# Encoder_Sheet2.net
KiCad netlist of a schematic drawn in Altium Designer
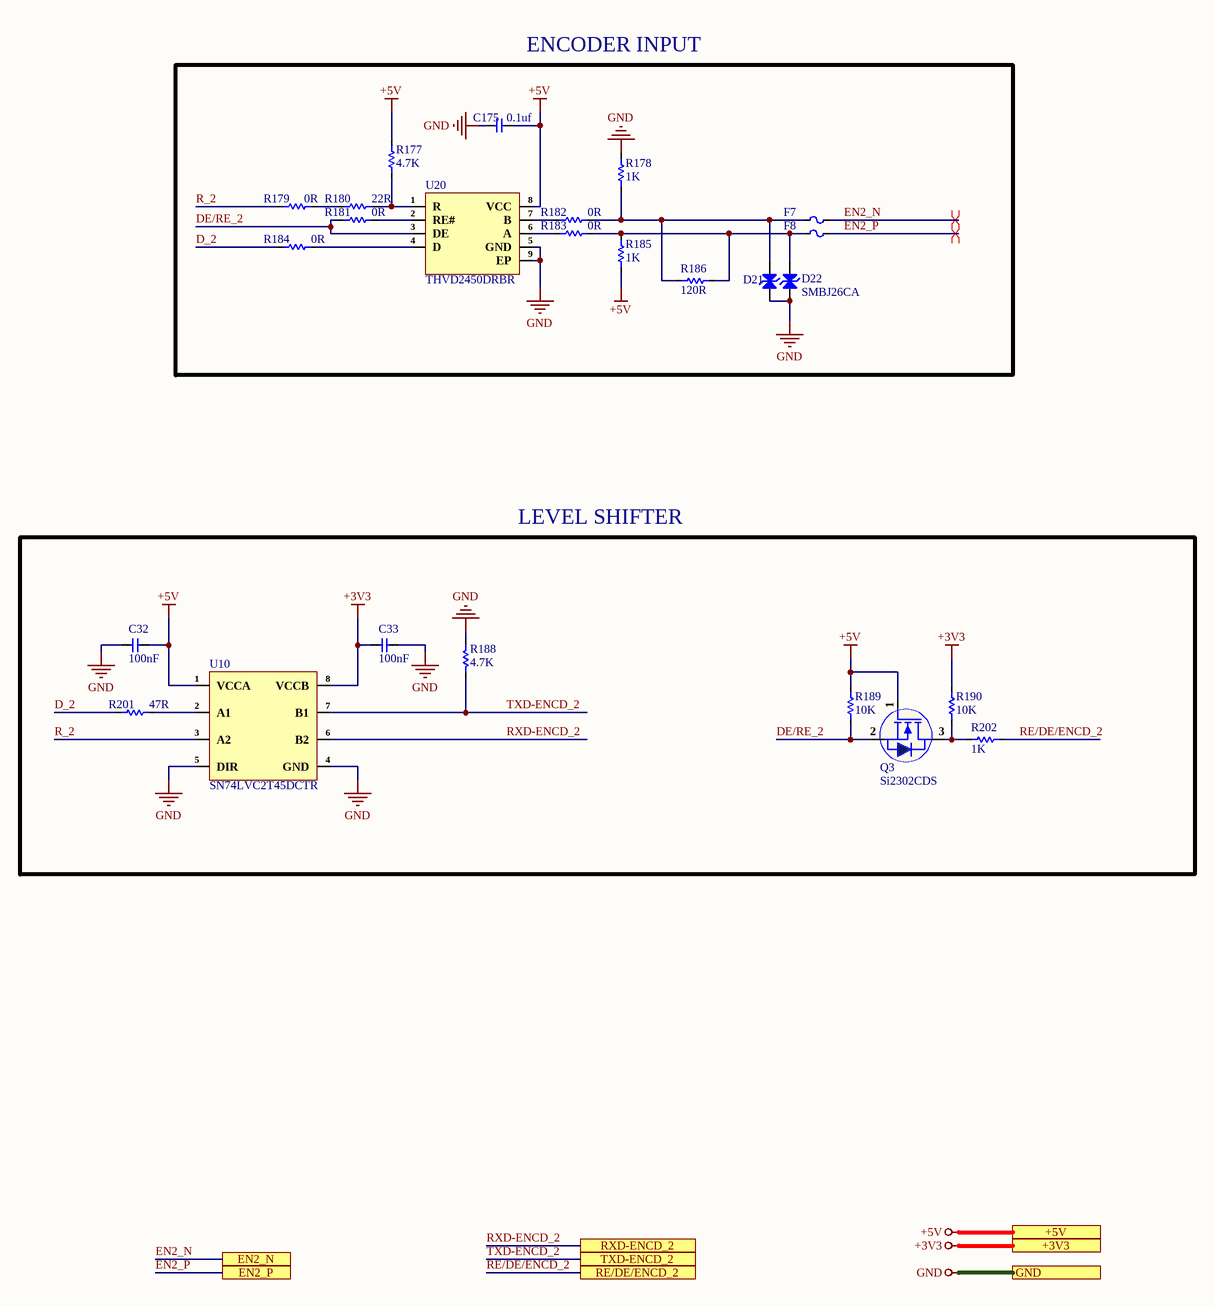
[diagram p0: Encoder_Sheet2.SchDoc]

(export (version "E")
  (design (tool "Eeschema 10.0.6"))
  (components
    (comp (ref "C32")
      (value "100nF")
      (footprint "cap-0402")
      (description "CAP CER 0.1UF 50V X7R 0402")
      (fields
        (field (name "MANUFACTURER") "TDK")
        (field (name "MANUFACTURER PART NUMBER") "C1005X7R1H104KT000F")
      )
      (libsource (lib "eSpark Libraries") (part "C1005X7R1H104KT000F"))
    )
    (comp (ref "C33")
      (value "100nF")
      (footprint "cap-0402")
      (description "CAP CER 0.1UF 50V X7R 0402")
      (fields
        (field (name "MANUFACTURER") "TDK")
        (field (name "MANUFACTURER PART NUMBER") "C1005X7R1H104KT000F")
      )
      (libsource (lib "eSpark Libraries") (part "C1005X7R1H104KT000F"))
    )
    (comp (ref "C175")
      (value "0.1uf")
      (footprint "Cap-0402")
      (description "CAP CER 0.1UF 100V X5R 0402")
      (fields
        (field (name "MANUFACTURER") "Murata")
        (field (name "MANUFACTURER PART NUMBER") "GRM155R62A104KE14D")
      )
      (libsource (lib "eSpark Libraries") (part "GRM155R62A104KE14D"))
    )
    (comp (ref "D21")
      (value "SMBJ26CA")
      (footprint "SMB Bi Directional")
      (description "SMB(DO-214AA) TVS ROHS")
      (fields (field (name "MANUFACTURER") "MSKSEMI") (field (name "LCSC PART NUMBER") "C5331111"))
      (libsource (lib "eSpark Libraries") (part "SMBJ26CA"))
    )
    (comp (ref "D22")
      (value "SMBJ26CA")
      (footprint "SMB Bi Directional")
      (description "SMB(DO-214AA) TVS ROHS")
      (fields (field (name "MANUFACTURER") "MSKSEMI") (field (name "LCSC PART NUMBER") "C5331111"))
      (libsource (lib "eSpark Libraries") (part "SMBJ26CA"))
    )
    (comp (ref "F7")
      (value "SMD0805P020TF")
      (footprint "Fuse-0805")
      (description "9V 200mA 100A 500mA 0805 Resettable Fuses ROHS")
      (fields (field (name "MANUFACTURER") "RUILON") (field (name "LCSC PART NUMBER") "C20976"))
      (libsource (lib "eSpark_centralized_Library(2022)") (part "SMD0805P020TF"))
    )
    (comp (ref "F8")
      (value "SMD0805P020TF")
      (footprint "Fuse-0805")
      (description "9V 200mA 100A 500mA 0805 Resettable Fuses ROHS")
      (fields (field (name "MANUFACTURER") "RUILON") (field (name "LCSC PART NUMBER") "C20976"))
      (libsource (lib "eSpark_centralized_Library(2022)") (part "SMD0805P020TF"))
    )
    (comp (ref "Q3")
      (value "Si2302CDS")
      (footprint "Sot-23")
      (description "N-CHANNEL 20-V (D-S) MOSFET")
      (fields
        (field (name "MANUFACTURER") "TECH PUBLIC")
        (field (name "MANUFACTURER PART NUMBER") "SI2302CDS")
      )
      (libsource (lib "eSpark_centralized_Library(2022)") (part "Si2302CDS"))
    )
    (comp (ref "R177")
      (value "4.7K")
      (footprint "Res-0402")
      (description "RES 4.7K OHM 1% 1/16W 0402")
      (fields
        (field (name "MANUFACTURER") "Yageo")
        (field (name "MANUFACTURER PART NUMBER") "RC0402FR-074K7L")
      )
      (libsource (lib "eSpark Libraries") (part "RC0402FR-074K7L"))
    )
    (comp (ref "R178")
      (value "1K")
      (footprint "Res-0402")
      (description "RES 1K OHM 1% 1/16W 0402")
      (fields
        (field (name "MANUFACTURER") "Yageo")
        (field (name "MANUFACTURER PART NUMBER") "RC0402FR-071KL")
      )
      (libsource (lib "eSpark Libraries") (part "RC0402FR-071KL"))
    )
    (comp (ref "R179")
      (value "0R")
      (footprint "Res-0603")
      (description "RES 0 OHM JUMPER 1/10W 0603")
      (fields
        (field (name "MANUFACTURER") "Yageo")
        (field (name "MANUFACTURER PART NUMBER") "RC0603JR-070RL")
      )
      (libsource (lib "eSpark Libraries") (part "RC0603JR-070RL"))
    )
    (comp (ref "R180")
      (value "22R")
      (footprint "Res-0402")
      (description "RES 22 OHM 1% 1/16W 0402")
      (fields
        (field (name "MANUFACTURER") "Yageo")
        (field (name "MANUFACTURER PART NUMBER") "RC0402FR-0722RL")
      )
      (libsource (lib "eSpark Libraries") (part "RC0402FR-0722RL"))
    )
    (comp (ref "R181")
      (value "0R")
      (footprint "Res-0603")
      (description "RES 0 OHM JUMPER 1/10W 0603")
      (fields
        (field (name "MANUFACTURER") "Yageo")
        (field (name "MANUFACTURER PART NUMBER") "RC0603JR-070RL")
      )
      (libsource (lib "eSpark Libraries") (part "RC0603JR-070RL"))
    )
    (comp (ref "R182")
      (value "0R")
      (footprint "Res-0603")
      (description "RES 0 OHM JUMPER 1/10W 0603")
      (fields
        (field (name "MANUFACTURER") "Yageo")
        (field (name "MANUFACTURER PART NUMBER") "RC0603JR-070RL")
      )
      (libsource (lib "eSpark Libraries") (part "RC0603JR-070RL"))
    )
    (comp (ref "R183")
      (value "0R")
      (footprint "Res-0603")
      (description "RES 0 OHM JUMPER 1/10W 0603")
      (fields
        (field (name "MANUFACTURER") "Yageo")
        (field (name "MANUFACTURER PART NUMBER") "RC0603JR-070RL")
      )
      (libsource (lib "eSpark Libraries") (part "RC0603JR-070RL"))
    )
    (comp (ref "R184")
      (value "0R")
      (footprint "Res-0603")
      (description "RES 0 OHM JUMPER 1/10W 0603")
      (fields
        (field (name "MANUFACTURER") "Yageo")
        (field (name "MANUFACTURER PART NUMBER") "RC0603JR-070RL")
      )
      (libsource (lib "eSpark Libraries") (part "RC0603JR-070RL"))
    )
    (comp (ref "R185")
      (value "1K")
      (footprint "Res-0402")
      (description "RES 1K OHM 1% 1/16W 0402")
      (fields
        (field (name "MANUFACTURER") "Yageo")
        (field (name "MANUFACTURER PART NUMBER") "RC0402FR-071KL")
      )
      (libsource (lib "eSpark Libraries") (part "RC0402FR-071KL"))
    )
    (comp (ref "R186")
      (value "120R")
      (footprint "Res-0402")
      (description "RES 120 OHM 1% 1/16W 0402")
      (fields
        (field (name "MANUFACTURER") "Yageo")
        (field (name "MANUFACTURER PART NUMBER") "RC0402FR-07120RL")
      )
      (libsource (lib "eSpark Libraries") (part "RC0402FR-07120RL"))
    )
    (comp (ref "R188")
      (value "4.7K")
      (footprint "Res-0402")
      (description "RES 4.7K OHM 1% 1/16W 0402")
      (fields
        (field (name "MANUFACTURER") "Yageo")
        (field (name "MANUFACTURER PART NUMBER") "RC0402FR-074K7L")
      )
      (libsource (lib "eSpark Libraries") (part "RC0402FR-074K7L"))
    )
    (comp (ref "R189")
      (value "10K")
      (footprint "Res-0402")
      (description "RES 10K OHM 1% 1/16W 0402")
      (fields
        (field (name "MANUFACTURER") "Yageo")
        (field (name "MANUFACTURER PART NUMBER") "RC0402FR-0710KL")
      )
      (libsource (lib "eSpark_centralized_Library(2022)") (part "RC0402FR-0710KL"))
    )
    (comp (ref "R190")
      (value "10K")
      (footprint "Res-0402")
      (description "RES 10K OHM 1% 1/16W 0402")
      (fields
        (field (name "MANUFACTURER") "Yageo")
        (field (name "MANUFACTURER PART NUMBER") "RC0402FR-0710KL")
      )
      (libsource (lib "eSpark_centralized_Library(2022)") (part "RC0402FR-0710KL"))
    )
    (comp (ref "R201")
      (value "47R")
      (footprint "Res-0402")
      (description "RES 47 OHM 1% 1/16W 0402")
      (fields
        (field (name "MANUFACTURER") "Yageo")
        (field (name "MANUFACTURER PART NUMBER") "RC0402FR-0747RL")
      )
      (libsource (lib "eSpark Libraries") (part "RC0402FR-0747RL"))
    )
    (comp (ref "R202")
      (value "1K")
      (footprint "Res-0603")
      (description "RES SMD 1K OHM 1% 1/10W 0603")
      (fields
        (field (name "MANUFACTURER") "Yageo")
        (field (name "MANUFACTURER PART NUMBER") "RC0603FR-071KL")
      )
      (libsource (lib "eSpark_centralized_Library(2022)") (part "RC0603FR-071KL"))
    )
    (comp (ref "U10")
      (value "SN74LVC2T45DCTR")
      (footprint "MSOP-8")
      (description "IC TRANSLATOR BIDIRECTIONAL SM8")
      (fields (field (name "LCSC PART NUMBER") "C22672") (field (name "MANUFACTURER") "Texas Instruments"))
      (libsource (lib "eSpark Libraries") (part "SN74LVC2T45DCTR"))
    )
    (comp (ref "U20")
      (value "THVD2450DRBR")
      (footprint "SON-8-EP(3x3)")
      (description "IC TRANSCEIVER HALF 1/1 8SON")
      (fields (field (name "MANUFACTURER") "Texas Instruments") (field (name "LCSC PART NUMBER") "C2878080"))
      (libsource (lib "eSpark Libraries") (part "THVD2450DRBR"))
    )
  )
  (nets
    (net (code "1") (name "+3V3") (class "Default")
      (node (ref "C33") (pin "1") (pinfunction "1_1") (pintype "passive"))
      (node (ref "R190") (pin "1") (pinfunction "1_1") (pintype "passive"))
      (node (ref "U10") (pin "8") (pinfunction "VCCB_8") (pintype "passive"))
    )
    (net (code "2") (name "+5V") (class "Default")
      (node (ref "C175") (pin "2") (pinfunction "2_2") (pintype "passive"))
      (node (ref "C32") (pin "1") (pinfunction "1_1") (pintype "passive"))
      (node (ref "Q3") (pin "1") (pinfunction "G_1") (pintype "passive"))
      (node (ref "R177") (pin "2") (pinfunction "2_2") (pintype "passive"))
      (node (ref "R185") (pin "1") (pinfunction "1_1") (pintype "passive"))
      (node (ref "R189") (pin "1") (pinfunction "1_1") (pintype "passive"))
      (node (ref "U10") (pin "1") (pinfunction "VCCA_1") (pintype "passive"))
      (node (ref "U20") (pin "8") (pinfunction "VCC_8") (pintype "passive"))
    )
    (net (code "3") (name "/DE{slash}RE_2") (class "Default")
      (node (ref "Q3") (pin "2") (pinfunction "S_2") (pintype "passive"))
      (node (ref "R181") (pin "1") (pinfunction "1_1") (pintype "passive"))
      (node (ref "R189") (pin "2") (pinfunction "2_2") (pintype "passive"))
      (node (ref "U20") (pin "3") (pinfunction "DE_3") (pintype "passive"))
    )
    (net (code "4") (name "/D_2") (class "Default")
      (node (ref "R184") (pin "1") (pinfunction "1_1") (pintype "passive"))
      (node (ref "R201") (pin "1") (pinfunction "1_1") (pintype "passive"))
    )
    (net (code "5") (name "/EN2_N") (class "Default")
      (node (ref "F7") (pin "2") (pinfunction "2_2") (pintype "passive"))
    )
    (net (code "6") (name "/EN2_P") (class "Default")
      (node (ref "F8") (pin "2") (pinfunction "2_2") (pintype "passive"))
    )
    (net (code "7") (name "/RE{slash}DE{slash}ENCD_2") (class "Default")
      (node (ref "R202") (pin "2") (pinfunction "2_2") (pintype "passive"))
    )
    (net (code "8") (name "/RXD-ENCD_2") (class "Default")
      (node (ref "U10") (pin "6") (pinfunction "B2_6") (pintype "passive"))
    )
    (net (code "9") (name "/R_2") (class "Default")
      (node (ref "R179") (pin "1") (pinfunction "1_1") (pintype "passive"))
      (node (ref "U10") (pin "3") (pinfunction "A2_3") (pintype "passive"))
    )
    (net (code "10") (name "/TXD-ENCD_2") (class "Default")
      (node (ref "R188") (pin "1") (pinfunction "1_1") (pintype "passive"))
      (node (ref "U10") (pin "7") (pinfunction "B1_7") (pintype "passive"))
    )
    (net (code "11") (name "GND") (class "Default")
      (node (ref "C175") (pin "1") (pinfunction "1_1") (pintype "passive"))
      (node (ref "C32") (pin "2") (pinfunction "2_2") (pintype "passive"))
      (node (ref "C33") (pin "2") (pinfunction "2_2") (pintype "passive"))
      (node (ref "D21") (pin "1") (pinfunction "A_1") (pintype "passive"))
      (node (ref "D22") (pin "1") (pinfunction "A_1") (pintype "passive"))
      (node (ref "R178") (pin "2") (pinfunction "2_2") (pintype "passive"))
      (node (ref "R188") (pin "2") (pinfunction "2_2") (pintype "passive"))
      (node (ref "U10") (pin "4") (pinfunction "GND_4") (pintype "passive"))
      (node (ref "U10") (pin "5") (pinfunction "DIR_5") (pintype "passive"))
      (node (ref "U20") (pin "5") (pinfunction "GND_5") (pintype "passive"))
      (node (ref "U20") (pin "9") (pinfunction "EP_9") (pintype "passive"))
    )
    (net (code "12") (name "Net-(D21-K)") (class "Default")
      (node (ref "D21") (pin "2") (pinfunction "K_2") (pintype "passive"))
      (node (ref "F7") (pin "1") (pinfunction "1_1") (pintype "passive"))
      (node (ref "R178") (pin "1") (pinfunction "1_1") (pintype "passive"))
      (node (ref "R182") (pin "2") (pinfunction "2_2") (pintype "passive"))
      (node (ref "R186") (pin "1") (pinfunction "1_1") (pintype "passive"))
    )
    (net (code "13") (name "Net-(D22-K)") (class "Default")
      (node (ref "D22") (pin "2") (pinfunction "K_2") (pintype "passive"))
      (node (ref "F8") (pin "1") (pinfunction "1_1") (pintype "passive"))
      (node (ref "R183") (pin "2") (pinfunction "2_2") (pintype "passive"))
      (node (ref "R185") (pin "2") (pinfunction "2_2") (pintype "passive"))
      (node (ref "R186") (pin "2") (pinfunction "2_2") (pintype "passive"))
    )
    (net (code "14") (name "Net-(Q3-D)") (class "Default")
      (node (ref "Q3") (pin "3") (pinfunction "D_3") (pintype "passive"))
      (node (ref "R190") (pin "2") (pinfunction "2_2") (pintype "passive"))
      (node (ref "R202") (pin "1") (pinfunction "1_1") (pintype "passive"))
    )
    (net (code "15") (name "Net-(R179-Pad2)") (class "Default")
      (node (ref "R179") (pin "2") (pinfunction "2_2") (pintype "passive"))
      (node (ref "R180") (pin "1") (pinfunction "1_1") (pintype "passive"))
    )
    (net (code "16") (name "Net-(U10-A1)") (class "Default")
      (node (ref "R201") (pin "2") (pinfunction "2_2") (pintype "passive"))
      (node (ref "U10") (pin "2") (pinfunction "A1_2") (pintype "passive"))
    )
    (net (code "17") (name "Net-(U20-A)") (class "Default")
      (node (ref "R183") (pin "1") (pinfunction "1_1") (pintype "passive"))
      (node (ref "U20") (pin "6") (pinfunction "A_6") (pintype "passive"))
    )
    (net (code "18") (name "Net-(U20-B)") (class "Default")
      (node (ref "R182") (pin "1") (pinfunction "1_1") (pintype "passive"))
      (node (ref "U20") (pin "7") (pinfunction "B_7") (pintype "passive"))
    )
    (net (code "19") (name "Net-(U20-D)") (class "Default")
      (node (ref "R184") (pin "2") (pinfunction "2_2") (pintype "passive"))
      (node (ref "U20") (pin "4") (pinfunction "D_4") (pintype "passive"))
    )
    (net (code "20") (name "Net-(U20-R)") (class "Default")
      (node (ref "R177") (pin "1") (pinfunction "1_1") (pintype "passive"))
      (node (ref "R180") (pin "2") (pinfunction "2_2") (pintype "passive"))
      (node (ref "U20") (pin "1") (pinfunction "R_1") (pintype "passive"))
    )
    (net (code "21") (name "Net-(U20-RE#)") (class "Default")
      (node (ref "R181") (pin "2") (pinfunction "2_2") (pintype "passive"))
      (node (ref "U20") (pin "2") (pinfunction "RE#_2") (pintype "passive"))
    )
  )
)
